# PM2565.net
KiCad netlist of a schematic drawn in Altium Designer
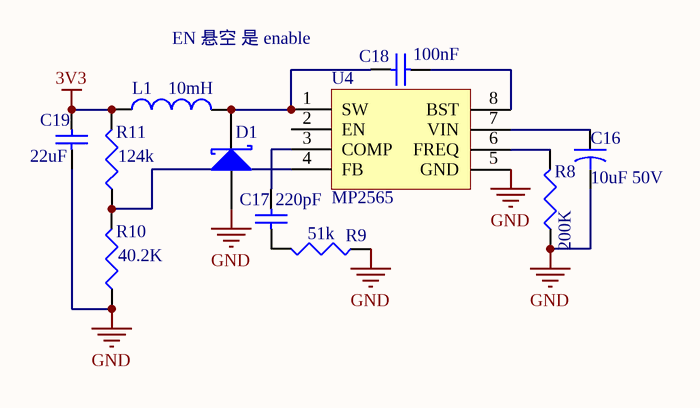
[diagram p0: PM2565.SchDoc]

(export (version "E")
  (design (tool "Eeschema 10.0.6"))
  (components
    (comp (ref "C16")
      (value "10uF 50V")
      (footprint "CAPR5-4X5")
      (description "Capacitor")
      (fields (field (name "PUBLISHER") "Altium Limited"))
      (libsource (lib "misc") (part "Cap2"))
    )
    (comp (ref "C17")
      (value "220pF")
      (footprint "0603_C")
      (fields (field (name "PUBLISHER") "Altium Limited"))
      (libsource (lib "misc") (part "Cap"))
    )
    (comp (ref "C18")
      (value "100nF")
      (footprint "0603_C")
      (fields (field (name "PUBLISHER") "Altium Limited"))
      (libsource (lib "misc") (part "Cap"))
    )
    (comp (ref "C19")
      (value "22uF")
      (footprint "0603_C")
      (fields (field (name "PUBLISHER") "Altium Limited"))
      (libsource (lib "misc") (part "Cap"))
    )
    (comp (ref "D1")
      (value "~")
      (footprint "B380")
      (description "Schottky Diode")
      (fields (field (name "PUBLISHER") "Altium Limited"))
      (libsource (lib "misc") (part "D Schottky"))
    )
    (comp (ref "L1")
      (value "10mH")
      (footprint "B380")
      (description "Inductor")
      (fields (field (name "PUBLISHER") "Altium Limited"))
      (libsource (lib "misc") (part "Ind"))
    )
    (comp (ref "R8")
      (value "200K")
      (footprint "0603_R")
      (fields (field (name "PUBLISHER") "Altium Limited"))
      (libsource (lib "misc") (part "Res"))
    )
    (comp (ref "R9")
      (value "51k")
      (footprint "0603_R")
      (fields (field (name "PUBLISHER") "Altium Limited"))
      (libsource (lib "misc") (part "Res"))
    )
    (comp (ref "R10")
      (value "40.2K")
      (footprint "0603_R")
      (fields (field (name "PUBLISHER") "Altium Limited"))
      (libsource (lib "misc") (part "Res"))
    )
    (comp (ref "R11")
      (value "124k")
      (footprint "0603_R")
      (fields (field (name "PUBLISHER") "Altium Limited"))
      (libsource (lib "misc") (part "Res"))
    )
    (comp (ref "U4")
      (value "MP2565")
      (footprint "SOIC8E")
      (description "50V  Step-Down Converter")
      (libsource (lib "misc1") (part "MP2565"))
    )
  )
  (nets
    (net (code "1") (name "3V3") (class "Default")
      (node (ref "C19") (pin "2") (pinfunction "2_2") (pintype "passive"))
      (node (ref "L1") (pin "1") (pinfunction "1_1") (pintype "passive"))
      (node (ref "R11") (pin "2") (pinfunction "2_2") (pintype "passive"))
    )
    (net (code "2") (name "GND") (class "Default")
      (node (ref "C16") (pin "2") (pinfunction "2_2") (pintype "passive"))
      (node (ref "C19") (pin "1") (pinfunction "1_1") (pintype "passive"))
      (node (ref "D1") (pin "1") (pinfunction "A_1") (pintype "passive"))
      (node (ref "R10") (pin "1") (pinfunction "1_1") (pintype "passive"))
      (node (ref "R8") (pin "1") (pinfunction "1_1") (pintype "passive"))
      (node (ref "R9") (pin "1") (pinfunction "1_1") (pintype "passive"))
      (node (ref "U4") (pin "5") (pinfunction "GND_5") (pintype "passive"))
    )
    (net (code "3") (name "Net-(C17-Pad1)") (class "Default")
      (node (ref "C17") (pin "1") (pinfunction "1_1") (pintype "passive"))
      (node (ref "R9") (pin "2") (pinfunction "2_2") (pintype "passive"))
    )
    (net (code "4") (name "Net-(D1-K)") (class "Default")
      (node (ref "C18") (pin "2") (pinfunction "2_2") (pintype "passive"))
      (node (ref "D1") (pin "2") (pinfunction "K_2") (pintype "passive"))
      (node (ref "L1") (pin "2") (pinfunction "2_2") (pintype "passive"))
      (node (ref "U4") (pin "1") (pinfunction "SW_1") (pintype "passive"))
    )
    (net (code "5") (name "Net-(U4-BST)") (class "Default")
      (node (ref "C18") (pin "1") (pinfunction "1_1") (pintype "passive"))
      (node (ref "U4") (pin "8") (pinfunction "BST_8") (pintype "passive"))
    )
    (net (code "6") (name "Net-(U4-COMP)") (class "Default")
      (node (ref "C17") (pin "2") (pinfunction "2_2") (pintype "passive"))
      (node (ref "U4") (pin "3") (pinfunction "COMP_3") (pintype "passive"))
    )
    (net (code "7") (name "Net-(U4-FB)") (class "Default")
      (node (ref "R10") (pin "2") (pinfunction "2_2") (pintype "passive"))
      (node (ref "R11") (pin "1") (pinfunction "1_1") (pintype "passive"))
      (node (ref "U4") (pin "4") (pinfunction "FB_4") (pintype "passive"))
    )
    (net (code "8") (name "Net-(U4-FREQ)") (class "Default")
      (node (ref "R8") (pin "2") (pinfunction "2_2") (pintype "passive"))
      (node (ref "U4") (pin "6") (pinfunction "FREQ_6") (pintype "passive"))
    )
    (net (code "9") (name "Net-(U4-VIN)") (class "Default")
      (node (ref "C16") (pin "1") (pinfunction "1_1") (pintype "passive"))
      (node (ref "U4") (pin "7") (pinfunction "VIN_7") (pintype "passive"))
    )
    (net (code "10") (name "unconnected-(U4-EN-Pad2)") (class "Default")
      (node (ref "U4") (pin "2") (pinfunction "EN_2") (pintype "passive"))
    )
  )
)
